# Power.net
KiCad netlist of a schematic drawn in Altium Designer
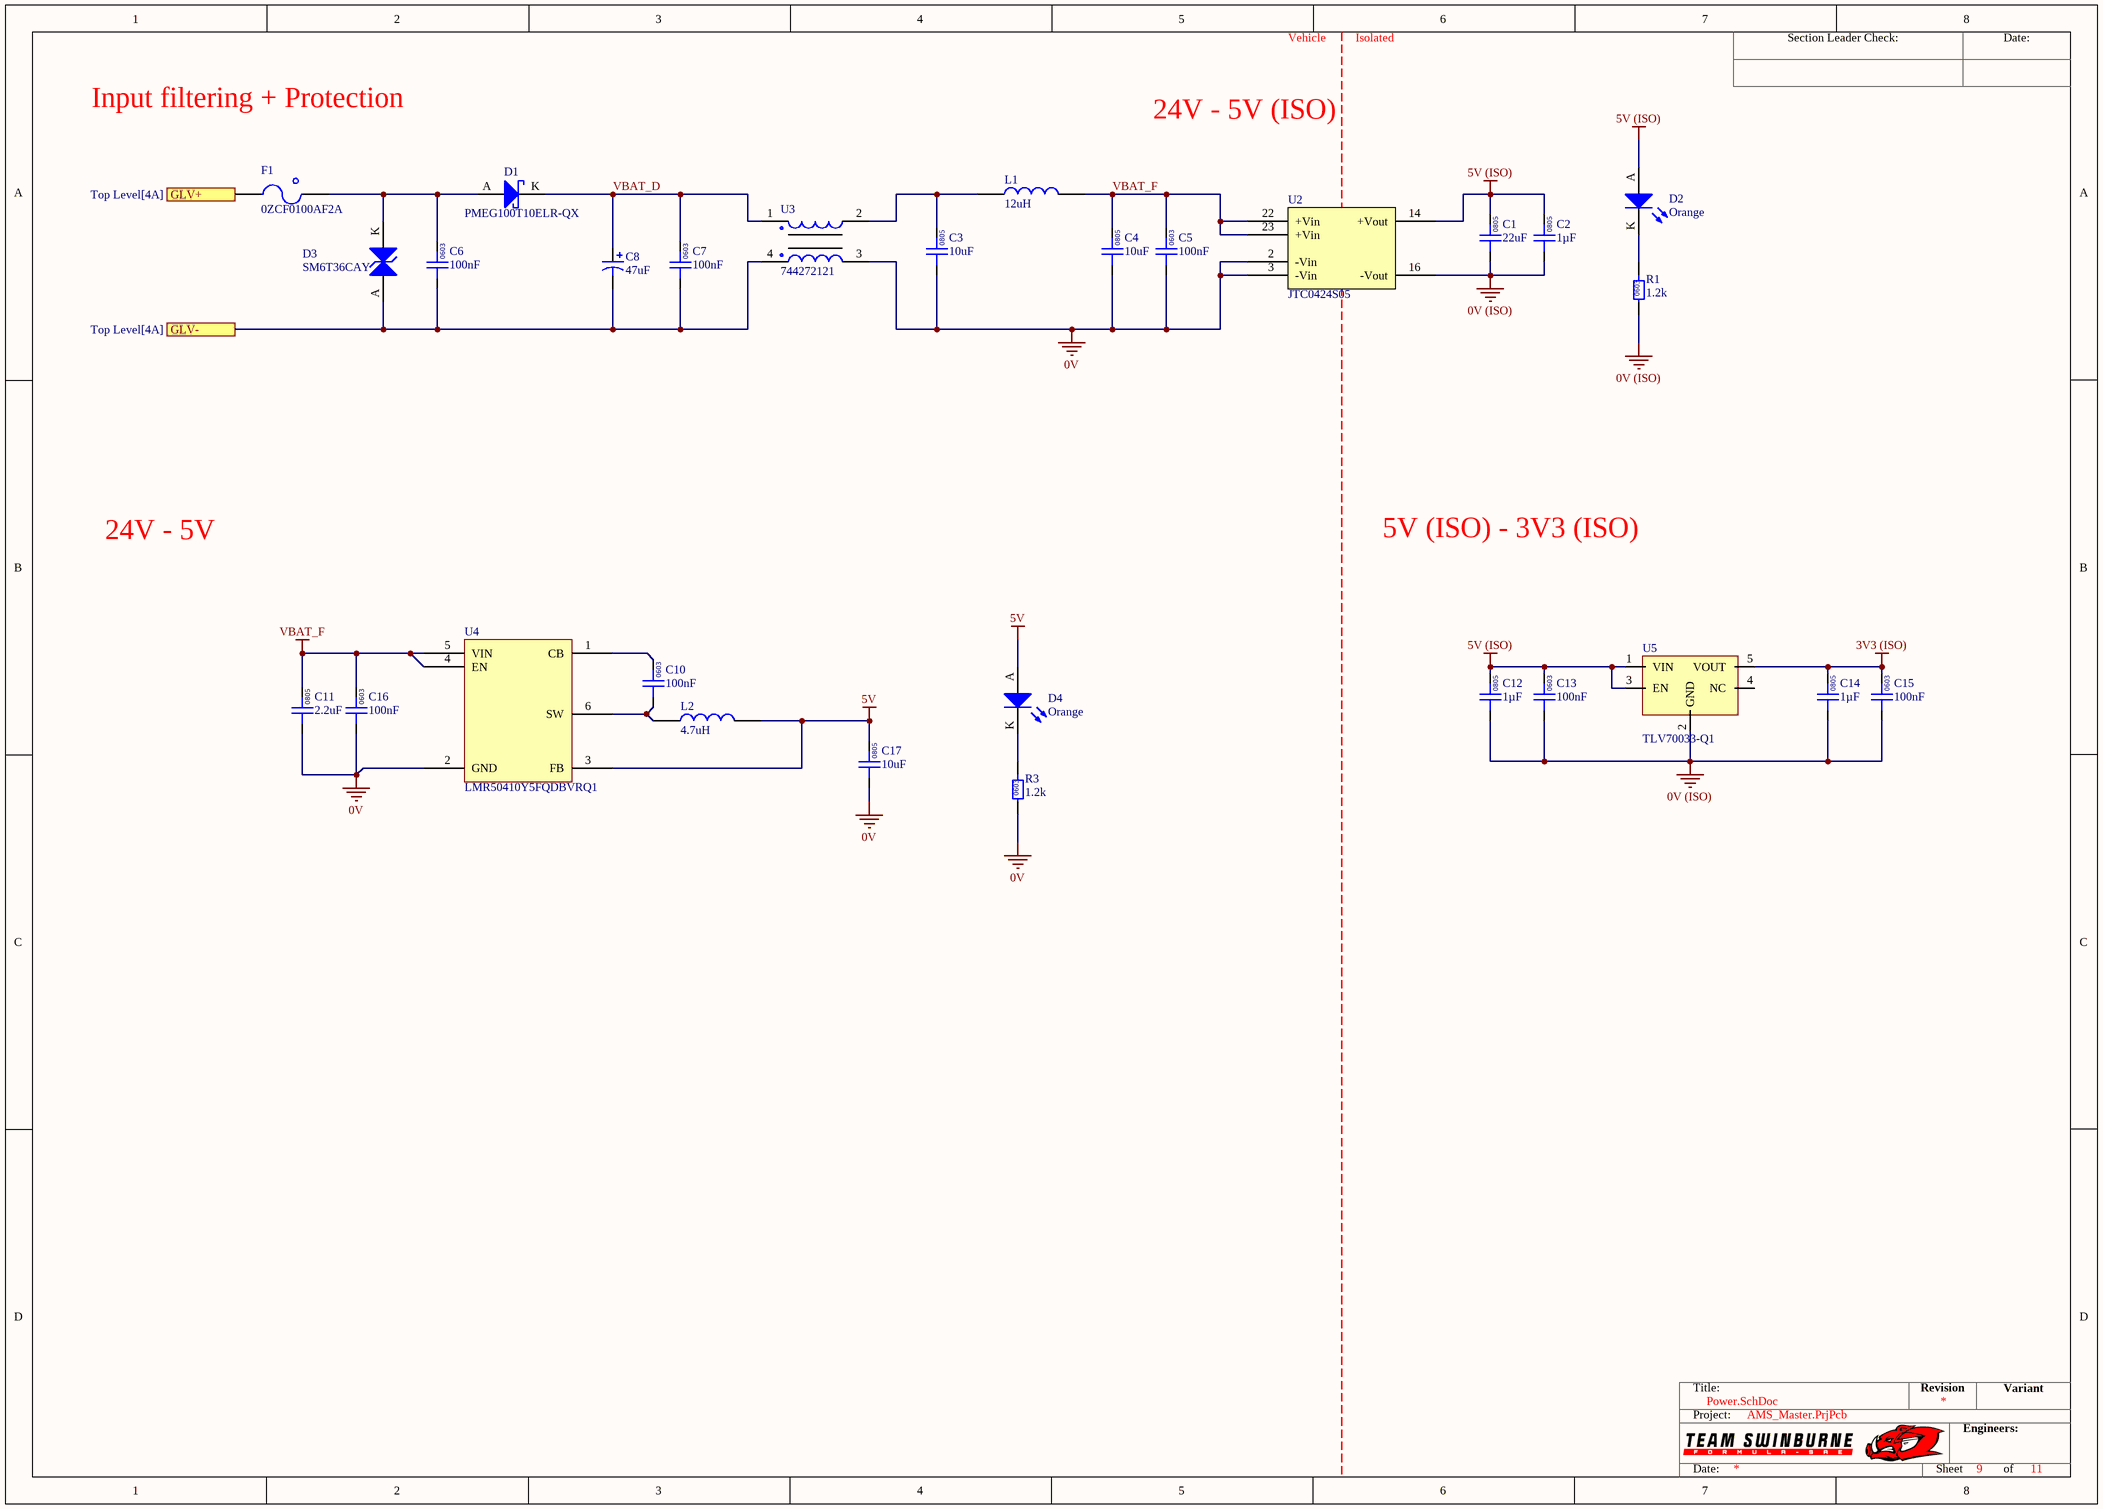
[diagram p0: Power.SchDoc]

(export (version "E")
  (design (tool "Eeschema 10.0.6"))
  (components
    (comp (ref "C1")
      (value "22uF")
      (footprint "0805")
      (fields
        (field (name "PART NUMBER") "GRM21BR61A226ME51L")
        (field (name "MANUFACTURER") "muRata")
        (field (name "TOLERANCE") "20%")
      )
      (libsource (lib "ts_standard_library") (part "Capacitor 0805"))
    )
    (comp (ref "C2")
      (value "1µF")
      (footprint "0805")
      (fields
        (field (name "PART NUMBER") "GCM21BR71H105KA03L")
        (field (name "MANUFACTURER") "muRata")
        (field (name "TOLERANCE") "±10%")
      )
      (libsource (lib "ts_standard_library") (part "Capacitor 0805"))
    )
    (comp (ref "C3")
      (value "10uF")
      (footprint "0805")
      (fields
        (field (name "PART NUMBER") "GRM21BR6YA106KE43L")
        (field (name "MANUFACTURER") "muRata")
        (field (name "TOLERANCE") "10%")
      )
      (libsource (lib "ts_standard_library") (part "Capacitor 0805"))
    )
    (comp (ref "C4")
      (value "10uF")
      (footprint "0805")
      (fields
        (field (name "PART NUMBER") "GRM21BR6YA106KE43L")
        (field (name "MANUFACTURER") "muRata")
        (field (name "TOLERANCE") "10%")
      )
      (libsource (lib "ts_standard_library") (part "Capacitor 0805"))
    )
    (comp (ref "C5")
      (value "100nF")
      (footprint "0603")
      (fields
        (field (name "PART NUMBER") "GCM188L81H104KA57D")
        (field (name "MANUFACTURER") "muRata")
        (field (name "TOLERANCE") "±10%")
      )
      (libsource (lib "ts_standard_library") (part "Capacitor 0603"))
    )
    (comp (ref "C6")
      (value "100nF")
      (footprint "0603")
      (fields
        (field (name "PART NUMBER") "GCM188L81H104KA57D")
        (field (name "MANUFACTURER") "muRata")
        (field (name "TOLERANCE") "±10%")
      )
      (libsource (lib "ts_standard_library") (part "Capacitor 0603"))
    )
    (comp (ref "C7")
      (value "100nF")
      (footprint "0603")
      (fields
        (field (name "PART NUMBER") "GCM188L81H104KA57D")
        (field (name "MANUFACTURER") "muRata")
        (field (name "TOLERANCE") "±10%")
      )
      (libsource (lib "ts_standard_library") (part "Capacitor 0603"))
    )
    (comp (ref "C8")
      (value "~")
      (footprint "CHEMI-CON ELCO")
      (fields
        (field (name "PART NUMBER") "HHXA350ARA470MF61G")
        (field (name "MANUFACTURER") "Chemi-Con")
        (field (name "TOLERANCE") "20%")
      )
      (libsource (lib "ts_standard_library") (part "Capacitor (Polarised)"))
    )
    (comp (ref "C10")
      (value "100nF")
      (footprint "0603")
      (fields
        (field (name "PART NUMBER") "GCM188L81H104KA57D")
        (field (name "MANUFACTURER") "muRata")
        (field (name "TOLERANCE") "±10%")
      )
      (libsource (lib "ts_standard_library") (part "Capacitor 0603"))
    )
    (comp (ref "C11")
      (value "2.2uF")
      (footprint "0805")
      (fields
        (field (name "PART NUMBER") "GRM21BR71E225KE11L")
        (field (name "MANUFACTURER") "Murata Electronics")
        (field (name "TOLERANCE") "±10%")
      )
      (libsource (lib "ts_standard_library") (part "Capacitor 0805"))
    )
    (comp (ref "C12")
      (value "1µF")
      (footprint "0805")
      (fields
        (field (name "PART NUMBER") "GCM21BR71H105KA03L")
        (field (name "MANUFACTURER") "muRata")
        (field (name "TOLERANCE") "±10%")
      )
      (libsource (lib "ts_standard_library") (part "Capacitor 0805"))
    )
    (comp (ref "C13")
      (value "100nF")
      (footprint "0603")
      (fields
        (field (name "PART NUMBER") "GCM188L81H104KA57D")
        (field (name "MANUFACTURER") "muRata")
        (field (name "TOLERANCE") "±10%")
      )
      (libsource (lib "ts_standard_library") (part "Capacitor 0603"))
    )
    (comp (ref "C14")
      (value "1µF")
      (footprint "0805")
      (fields
        (field (name "PART NUMBER") "GCM21BR71H105KA03L")
        (field (name "MANUFACTURER") "muRata")
        (field (name "TOLERANCE") "±10%")
      )
      (libsource (lib "ts_standard_library") (part "Capacitor 0805"))
    )
    (comp (ref "C15")
      (value "100nF")
      (footprint "0603")
      (fields
        (field (name "PART NUMBER") "GCM188L81H104KA57D")
        (field (name "MANUFACTURER") "muRata")
        (field (name "TOLERANCE") "±10%")
      )
      (libsource (lib "ts_standard_library") (part "Capacitor 0603"))
    )
    (comp (ref "C16")
      (value "100nF")
      (footprint "0603")
      (fields
        (field (name "PART NUMBER") "GCM188L81H104KA57D")
        (field (name "MANUFACTURER") "muRata")
        (field (name "TOLERANCE") "±10%")
      )
      (libsource (lib "ts_standard_library") (part "Capacitor 0603"))
    )
    (comp (ref "C17")
      (value "10uF")
      (footprint "0805")
      (fields
        (field (name "PART NUMBER") "GRM21BR6YA106KE43L")
        (field (name "MANUFACTURER") "muRata")
        (field (name "TOLERANCE") "10%")
      )
      (libsource (lib "ts_standard_library") (part "Capacitor 0805"))
    )
    (comp (ref "D1")
      (value "PMEG100T10ELR-QX")
      (footprint "NXP SOD123W")
      (fields
        (field (name "MANUFACTURER") "Nexperia USA Inc.")
        (field (name "DIGIKEY PART NUMBER") "1727-PMEG100T10ELR-QXCT-ND")
      )
      (libsource (lib "ts_standard_library") (part "Diode (Schottky)"))
    )
    (comp (ref "D2")
      (value "Orange")
      (footprint "0805 LED")
      (description "Orange LED Indication - Discrete 1.75V 0805 (2012 Metric)")
      (fields (field (name "PART NUMBER") "SML-211DTT86") (field (name "MANUFACTURER") "ROHM Semiconductor"))
      (libsource (lib "ts_standard_library") (part "LED"))
    )
    (comp (ref "D3")
      (value "SM6T36CAY")
      (footprint "ST SMB DIODE")
      (fields
        (field (name "MANUFACTURER") "STMicroelectronics")
        (field (name "DIGIKEY PART NUMBER") "497-10804-1-ND")
      )
      (libsource (lib "ts_standard_library") (part "TVS (Bidirectional)"))
    )
    (comp (ref "D4")
      (value "Orange")
      (footprint "0805 LED")
      (description "Orange LED Indication - Discrete 1.75V 0805 (2012 Metric)")
      (fields (field (name "PART NUMBER") "SML-211DTT86") (field (name "MANUFACTURER") "ROHM Semiconductor"))
      (libsource (lib "ts_standard_library") (part "LED"))
    )
    (comp (ref "F1")
      (value "0ZCF0100AF2A")
      (footprint "2920")
      (description "PTC RESET FUSE 60V 1A 292")
      (fields
        (field (name "MANUFACTURER") "Littelfuse Inc.")
        (field (name "DIGIKEY PART NUMBER") "507-2070-1-ND")
      )
      (libsource (lib "ts_standard_library") (part "PTC Fuse"))
    )
    (comp (ref "L1")
      (value "12uH")
      (footprint "1812")
      (fields
        (field (name "PART NUMBER") "RLS-126")
        (field (name "MANUFACTURER") "Recom")
        (field (name "TOLERANCE") "0.2")
      )
      (libsource (lib "ts_standard_library") (part "Inductor"))
    )
    (comp (ref "L2")
      (value "4.7uH")
      (footprint "SRN3015TA-4R7M")
      (fields
        (field (name "PART NUMBER") "SRN4018-4R7M")
        (field (name "MANUFACTURER") "Bourns")
        (field (name "TOLERANCE") "0.2")
      )
      (libsource (lib "ts_standard_library") (part "Inductor"))
    )
    (comp (ref "R1")
      (value "1.2k")
      (footprint "0603")
      (fields
        (field (name "PART NUMBER") "RC0603JR-071K2L")
        (field (name "MANUFACTURER") "YAGEO")
        (field (name "TOLERANCE") "0.01")
      )
      (libsource (lib "ts_standard_library") (part "Resistor 0603"))
    )
    (comp (ref "R3")
      (value "1.2k")
      (footprint "0603")
      (fields
        (field (name "PART NUMBER") "RC0603JR-071K2L")
        (field (name "MANUFACTURER") "YAGEO")
        (field (name "TOLERANCE") "0.01")
      )
      (libsource (lib "ts_standard_library") (part "Resistor 0603"))
    )
    (comp (ref "U2")
      (value "JTC0424S05")
      (footprint "24-DIP Module, 7 Leads")
      (description "DC DC CONVERTER 5V 4W")
      (fields (field (name "MANUFACTURER") "XP Power") (field (name "DIGIKEY PART NUMBER") "JTC0424S05-ND"))
      (libsource (lib "ts_20-standard-library") (part "JTC0424S05"))
    )
    (comp (ref "U3")
      (value "744272121")
      (footprint "Wurth 4-PC Pad")
      (fields
        (field (name "MANUFACTURER") "Wurth Electronics Inc")
        (field (name "DIGIKEY PART NUMBER") "732-1489-1-ND")
      )
      (libsource (lib "ts_standard_library") (part "CM Choke"))
    )
    (comp (ref "U4")
      (value "LMR50410Y5FQDBVRQ1")
      (footprint "TI-SOT23-6")
      (description "IC REG BUCK 5V 1A SOT23-6")
      (fields (field (name "PART NUMBER") "LMR50410-Q1") (field (name "MANUFACTURER") "Texas Instruments"))
      (libsource (lib "ts_standard_library") (part "LMR50410Y5FQDBVRQ1"))
    )
    (comp (ref "U5")
      (value "TLV70033-Q1")
      (footprint "TI SOT-23-5")
      (description "IC REG LINEAR 3.3V 200MA SOT23-5")
      (fields
        (field (name "MANUFACTURER") "Texas Instruments")
        (field (name "DIGIKEY PART NUMBER") "296-27780-1-ND")
      )
      (libsource (lib "ts_standard_library") (part "TLV70033-Q1"))
    )
  )
  (nets
    (net (code "1") (name "/GLV+") (class "Default")
      (node (ref "F1") (pin "1") (pinfunction "1_1") (pintype "passive"))
    )
    (net (code "2") (name "/GLV-") (class "Default")
      (node (ref "C6") (pin "1") (pinfunction "1_1") (pintype "passive"))
      (node (ref "C7") (pin "1") (pinfunction "1_1") (pintype "passive"))
      (node (ref "C8") (pin "1") (pinfunction "1_1") (pintype "passive"))
      (node (ref "D3") (pin "A") (pinfunction "A_A") (pintype "passive"))
      (node (ref "U3") (pin "4") (pinfunction "4_4") (pintype "passive"))
    )
    (net (code "3") (name "/VBAT_D") (class "Default")
      (node (ref "C7") (pin "2") (pinfunction "2_2") (pintype "passive"))
      (node (ref "C8") (pin "2") (pinfunction "2_2") (pintype "passive"))
      (node (ref "D1") (pin "K") (pinfunction "K_K") (pintype "passive"))
      (node (ref "U3") (pin "1") (pinfunction "1_1") (pintype "passive"))
    )
    (net (code "4") (name "0V") (class "Default")
      (node (ref "C11") (pin "1") (pinfunction "1_1") (pintype "passive"))
      (node (ref "C16") (pin "1") (pinfunction "1_1") (pintype "passive"))
      (node (ref "C17") (pin "1") (pinfunction "1_1") (pintype "passive"))
      (node (ref "C3") (pin "1") (pinfunction "1_1") (pintype "passive"))
      (node (ref "C4") (pin "1") (pinfunction "1_1") (pintype "passive"))
      (node (ref "C5") (pin "1") (pinfunction "1_1") (pintype "passive"))
      (node (ref "R3") (pin "1") (pinfunction "1_1") (pintype "passive"))
      (node (ref "U2") (pin "2") (pinfunction "-Vin_2") (pintype "passive"))
      (node (ref "U2") (pin "3") (pinfunction "-Vin_3") (pintype "passive"))
      (node (ref "U3") (pin "3") (pinfunction "3_3") (pintype "power_in"))
      (node (ref "U4") (pin "2") (pinfunction "GND_2") (pintype "passive"))
    )
    (net (code "5") (name "0V (ISO)") (class "Default")
      (node (ref "C1") (pin "1") (pinfunction "1_1") (pintype "passive"))
      (node (ref "C12") (pin "1") (pinfunction "1_1") (pintype "passive"))
      (node (ref "C13") (pin "1") (pinfunction "1_1") (pintype "passive"))
      (node (ref "C14") (pin "1") (pinfunction "1_1") (pintype "passive"))
      (node (ref "C15") (pin "1") (pinfunction "1_1") (pintype "passive"))
      (node (ref "C2") (pin "1") (pinfunction "1_1") (pintype "passive"))
      (node (ref "R1") (pin "1") (pinfunction "1_1") (pintype "passive"))
      (node (ref "U2") (pin "16") (pinfunction "-Vout_16") (pintype "passive"))
      (node (ref "U5") (pin "2") (pinfunction "GND_2") (pintype "passive"))
    )
    (net (code "6") (name "3V3 (ISO)") (class "Default")
      (node (ref "C14") (pin "2") (pinfunction "2_2") (pintype "passive"))
      (node (ref "C15") (pin "2") (pinfunction "2_2") (pintype "passive"))
      (node (ref "U5") (pin "5") (pinfunction "VOUT_5") (pintype "passive"))
    )
    (net (code "7") (name "5V") (class "Default")
      (node (ref "C17") (pin "2") (pinfunction "2_2") (pintype "passive"))
      (node (ref "D4") (pin "A") (pinfunction "A_A") (pintype "passive"))
      (node (ref "L2") (pin "1") (pinfunction "1_1") (pintype "passive"))
      (node (ref "U4") (pin "3") (pinfunction "FB_3") (pintype "passive"))
    )
    (net (code "8") (name "5V (ISO)") (class "Default")
      (node (ref "C1") (pin "2") (pinfunction "2_2") (pintype "passive"))
      (node (ref "C12") (pin "2") (pinfunction "2_2") (pintype "passive"))
      (node (ref "C13") (pin "2") (pinfunction "2_2") (pintype "passive"))
      (node (ref "C2") (pin "2") (pinfunction "2_2") (pintype "passive"))
      (node (ref "D2") (pin "A") (pinfunction "A_A") (pintype "passive"))
      (node (ref "U2") (pin "14") (pinfunction "+Vout_14") (pintype "passive"))
      (node (ref "U5") (pin "1") (pinfunction "VIN_1") (pintype "passive"))
      (node (ref "U5") (pin "3") (pinfunction "EN_3") (pintype "passive"))
    )
    (net (code "9") (name "Net-(C3-Pad2)") (class "Default")
      (node (ref "C3") (pin "2") (pinfunction "2_2") (pintype "passive"))
      (node (ref "L1") (pin "2") (pinfunction "2_2") (pintype "passive"))
      (node (ref "U3") (pin "2") (pinfunction "2_2") (pintype "passive"))
    )
    (net (code "10") (name "Net-(C6-Pad2)") (class "Default")
      (node (ref "C6") (pin "2") (pinfunction "2_2") (pintype "passive"))
      (node (ref "D1") (pin "A") (pinfunction "A_A") (pintype "passive"))
      (node (ref "D3") (pin "K") (pinfunction "K_K") (pintype "passive"))
      (node (ref "F1") (pin "2") (pinfunction "2_2") (pintype "passive"))
    )
    (net (code "11") (name "Net-(D2-PadK)") (class "Default")
      (node (ref "D2") (pin "K") (pinfunction "K_K") (pintype "passive"))
      (node (ref "R1") (pin "2") (pinfunction "2_2") (pintype "passive"))
    )
    (net (code "12") (name "Net-(D4-PadK)") (class "Default")
      (node (ref "D4") (pin "K") (pinfunction "K_K") (pintype "passive"))
      (node (ref "R3") (pin "2") (pinfunction "2_2") (pintype "passive"))
    )
    (net (code "13") (name "Net-(U4-CB)") (class "Default")
      (node (ref "C10") (pin "2") (pinfunction "2_2") (pintype "passive"))
      (node (ref "U4") (pin "1") (pinfunction "CB_1") (pintype "passive"))
    )
    (net (code "14") (name "Net-(U4-SW)") (class "Default")
      (node (ref "C10") (pin "1") (pinfunction "1_1") (pintype "passive"))
      (node (ref "L2") (pin "2") (pinfunction "2_2") (pintype "passive"))
      (node (ref "U4") (pin "6") (pinfunction "SW_6") (pintype "passive"))
    )
    (net (code "15") (name "VBAT_F") (class "Default")
      (node (ref "C11") (pin "2") (pinfunction "2_2") (pintype "passive"))
      (node (ref "C16") (pin "2") (pinfunction "2_2") (pintype "passive"))
      (node (ref "C4") (pin "2") (pinfunction "2_2") (pintype "passive"))
      (node (ref "C5") (pin "2") (pinfunction "2_2") (pintype "passive"))
      (node (ref "L1") (pin "1") (pinfunction "1_1") (pintype "passive"))
      (node (ref "U2") (pin "22") (pinfunction "+Vin_22") (pintype "passive"))
      (node (ref "U2") (pin "23") (pinfunction "+Vin_23") (pintype "passive"))
      (node (ref "U4") (pin "4") (pinfunction "EN_4") (pintype "passive"))
      (node (ref "U4") (pin "5") (pinfunction "VIN_5") (pintype "passive"))
    )
    (net (code "16") (name "unconnected-(U5-NC-Pad4)") (class "Default")
      (node (ref "U5") (pin "4") (pinfunction "NC_4") (pintype "passive"))
    )
  )
)
